# BMP390.net
KiCad netlist of a schematic drawn in Altium Designer
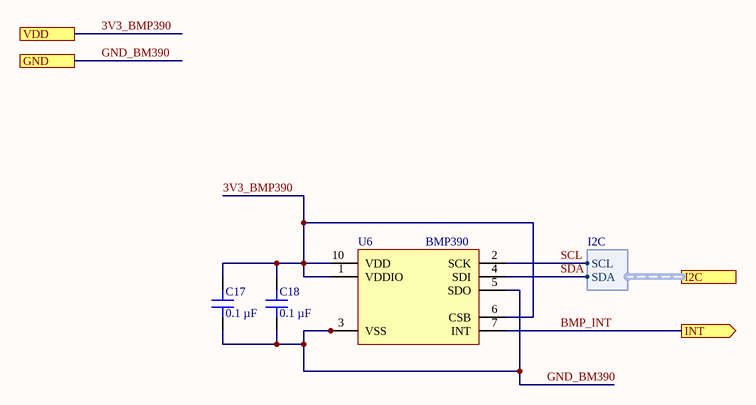
[diagram p0: BMP390.SchDoc]

(export (version "E")
  (design (tool "Eeschema 10.0.6"))
  (components
    (comp (ref "C17")
      (value "0.1 µF")
      (footprint "CAP 0402_1005")
      (description "CAP CER 0.1UF 16V X7R 0402")
      (fields (field (name "PART NUMBER") "C0402C104K4RACAUTO") (field (name "MANUFACTURER") "KEMET"))
      (libsource (lib "Celestial Altium Library - altium_library") (part "Capacitor"))
    )
    (comp (ref "C18")
      (value "0.1 µF")
      (footprint "CAP 0402_1005")
      (description "CAP CER 0.1UF 16V X7R 0402")
      (fields (field (name "PART NUMBER") "C0402C104K4RACAUTO") (field (name "MANUFACTURER") "KEMET"))
      (libsource (lib "Celestial Altium Library - altium_library") (part "Capacitor"))
    )
    (comp (ref "U6")
      (value "BMP390")
      (footprint "BMP390L")
      (description "Altimeter")
      (libsource (lib "IC") (part "BMP390"))
    )
  )
  (nets
    (net (code "2") (name "/3V3_BMP390") (class "Default")
      (node (ref "C17") (pin "2") (pinfunction "2_2") (pintype "passive"))
      (node (ref "C18") (pin "2") (pinfunction "2_2") (pintype "passive"))
      (node (ref "U6") (pin "1") (pinfunction "VDDIO_1") (pintype "passive"))
      (node (ref "U6") (pin "10") (pinfunction "VDD_10") (pintype "passive"))
      (node (ref "U6") (pin "6") (pinfunction "CSB_6") (pintype "passive"))
    )
    (net (code "3") (name "/BMP_INT") (class "Default")
      (node (ref "U6") (pin "7") (pinfunction "INT_7") (pintype "passive"))
    )
    (net (code "4") (name "/GND_BM390") (class "Default")
      (node (ref "C17") (pin "1") (pinfunction "1_1") (pintype "passive"))
      (node (ref "C18") (pin "1") (pinfunction "1_1") (pintype "passive"))
      (node (ref "U6") (pin "3") (pinfunction "VSS_3") (pintype "passive"))
      (node (ref "U6") (pin "5") (pinfunction "SDO_5") (pintype "passive"))
      (node (ref "U6") (pin "8") (pinfunction "VSS_8") (pintype "passive"))
      (node (ref "U6") (pin "9") (pinfunction "VSS_9") (pintype "passive"))
    )
    (net (code "5") (name "/SCL") (class "Default")
      (node (ref "U6") (pin "2") (pinfunction "SCK_2") (pintype "passive"))
    )
    (net (code "6") (name "/SDA") (class "Default")
      (node (ref "U6") (pin "4") (pinfunction "SDI_4") (pintype "passive"))
    )
  )
)
